# BMS_Carrier_-_Firmware_Contactor_Control.net
KiCad netlist of a schematic drawn in Altium Designer
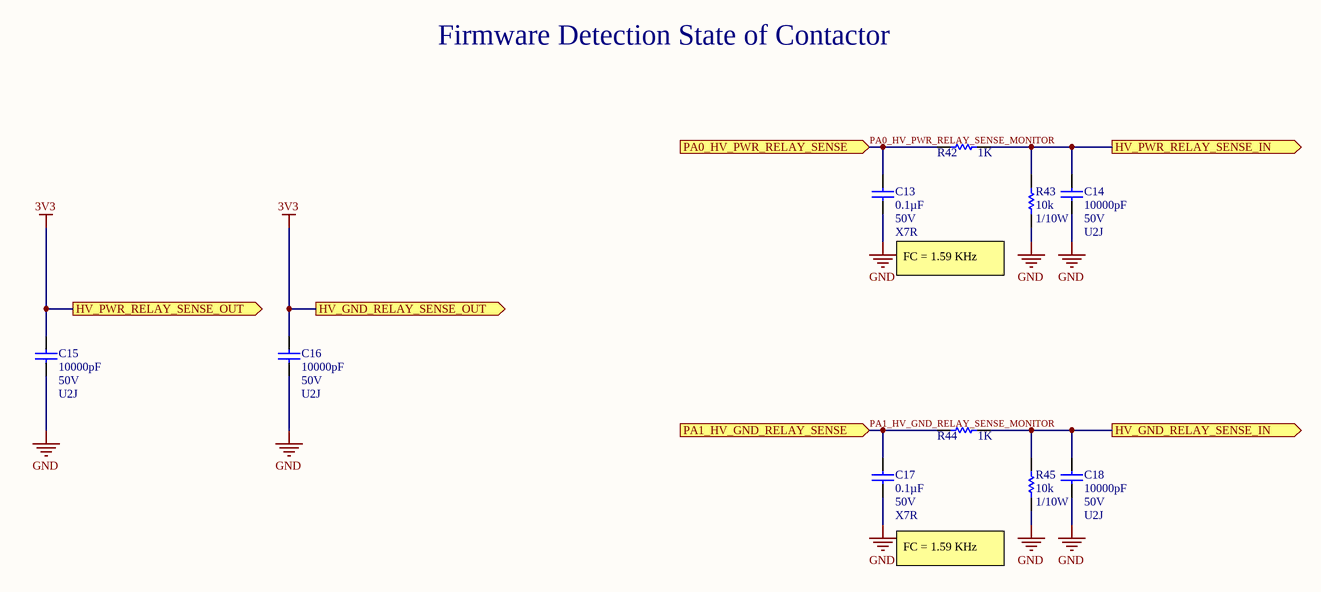
[diagram p0: BMS Carrier - Firmware Contactor Control.SchDoc]

(export (version "E")
  (design (tool "Eeschema 10.0.6"))
  (components
    (comp (ref "C13")
      (value "CAP CER 0.1UF 50V 10% X7R 0603")
      (footprint "CAP, 0603")
      (description "0.10µF ±10% 50V Ceramic Capacitor X7R 0603 (1608 Metric)")
      (fields
        (field (name "TOLERANCE") "±10%")
        (field (name "CAPACITANCE") "0.1µF")
        (field (name "VOLTAGE") "50V")
        (field (name "TEMPERATURE COEFFICIENT") "X7R")
      )
      (libsource (lib "Schematic Diagrams") (part "CAP CER 0.1UF 50V 10% X7R 0603"))
    )
    (comp (ref "C14")
      (value "CAP CER 10nF 50V 5% X7R 0603")
      (footprint "CAP, 0603")
      (description "10000pF ±5% 50V Ceramic Capacitor U2J 0603 (1608 Metric)")
      (fields
        (field (name "TOLERANCE") "±5%")
        (field (name "CAPACITANCE") "10000pF")
        (field (name "VOLTAGE") "50V")
        (field (name "TEMPERATURE COEFFICIENT") "U2J")
      )
      (libsource (lib "Schematic Diagrams") (part "CAP CER 10nF 50V 5% X7R 0603"))
    )
    (comp (ref "C15")
      (value "CAP CER 10nF 50V 5% X7R 0603")
      (footprint "CAP, 0603")
      (description "10000pF ±5% 50V Ceramic Capacitor U2J 0603 (1608 Metric)")
      (fields
        (field (name "TOLERANCE") "±5%")
        (field (name "CAPACITANCE") "10000pF")
        (field (name "VOLTAGE") "50V")
        (field (name "TEMPERATURE COEFFICIENT") "U2J")
      )
      (libsource (lib "Schematic Diagrams") (part "CAP CER 10nF 50V 5% X7R 0603"))
    )
    (comp (ref "C16")
      (value "CAP CER 10nF 50V 5% X7R 0603")
      (footprint "CAP, 0603")
      (description "10000pF ±5% 50V Ceramic Capacitor U2J 0603 (1608 Metric)")
      (fields
        (field (name "TOLERANCE") "±5%")
        (field (name "CAPACITANCE") "10000pF")
        (field (name "VOLTAGE") "50V")
        (field (name "TEMPERATURE COEFFICIENT") "U2J")
      )
      (libsource (lib "Schematic Diagrams") (part "CAP CER 10nF 50V 5% X7R 0603"))
    )
    (comp (ref "C17")
      (value "CAP CER 0.1UF 50V 10% X7R 0603")
      (footprint "CAP, 0603")
      (description "0.10µF ±10% 50V Ceramic Capacitor X7R 0603 (1608 Metric)")
      (fields
        (field (name "TOLERANCE") "±10%")
        (field (name "CAPACITANCE") "0.1µF")
        (field (name "VOLTAGE") "50V")
        (field (name "TEMPERATURE COEFFICIENT") "X7R")
      )
      (libsource (lib "Schematic Diagrams") (part "CAP CER 0.1UF 50V 10% X7R 0603"))
    )
    (comp (ref "C18")
      (value "CAP CER 10nF 50V 5% X7R 0603")
      (footprint "CAP, 0603")
      (description "10000pF ±5% 50V Ceramic Capacitor U2J 0603 (1608 Metric)")
      (fields
        (field (name "TOLERANCE") "±5%")
        (field (name "CAPACITANCE") "10000pF")
        (field (name "VOLTAGE") "50V")
        (field (name "TEMPERATURE COEFFICIENT") "U2J")
      )
      (libsource (lib "Schematic Diagrams") (part "CAP CER 10nF 50V 5% X7R 0603"))
    )
    (comp (ref "R42")
      (value "1K")
      (footprint "RES, 0603")
      (description "1k Ohm ±5% 0.1W, 1/10W Chip Resistor 0603 (1608 Metric)")
      (fields
        (field (name "MANUFACTURER") "Yageo")
        (field (name "MANUFACTURER PART NUMBER") "RC0603JR-071KL")
      )
      (libsource (lib "Schematic Diagrams") (part "RES 1K OHM 5% 1/10W 0603"))
    )
    (comp (ref "R43")
      (value "RES 10K OHM 1% 1/10W 0603")
      (footprint "RES, 0603")
      (description "RES SMD 10K OHM 1% 1/10W 0603")
      (fields
        (field (name "TOLERANCE") "±1%")
        (field (name "RESISTANCE") "10k")
        (field (name "POWER") "1/10W")
      )
      (libsource (lib "Schematic Diagrams") (part "RES 10K OHM 1% 1/10W 0603"))
    )
    (comp (ref "R44")
      (value "1K")
      (footprint "RES, 0603")
      (description "1k Ohm ±5% 0.1W, 1/10W Chip Resistor 0603 (1608 Metric)")
      (fields
        (field (name "MANUFACTURER") "Yageo")
        (field (name "MANUFACTURER PART NUMBER") "RC0603JR-071KL")
      )
      (libsource (lib "Schematic Diagrams") (part "RES 1K OHM 5% 1/10W 0603"))
    )
    (comp (ref "R45")
      (value "RES 10K OHM 1% 1/10W 0603")
      (footprint "RES, 0603")
      (description "RES SMD 10K OHM 1% 1/10W 0603")
      (fields
        (field (name "TOLERANCE") "±1%")
        (field (name "RESISTANCE") "10k")
        (field (name "POWER") "1/10W")
      )
      (libsource (lib "Schematic Diagrams") (part "RES 10K OHM 1% 1/10W 0603"))
    )
  )
  (nets
    (net (code "1") (name "/HV_GND_RELAY_SENSE_IN") (class "Default")
      (node (ref "C18") (pin "1") (pinfunction "1_1") (pintype "passive"))
      (node (ref "R44") (pin "2") (pinfunction "2_2") (pintype "passive"))
      (node (ref "R45") (pin "1") (pinfunction "1_1") (pintype "passive"))
    )
    (net (code "2") (name "/HV_PWR_RELAY_SENSE_IN") (class "Default")
      (node (ref "C14") (pin "1") (pinfunction "1_1") (pintype "passive"))
      (node (ref "R42") (pin "2") (pinfunction "2_2") (pintype "passive"))
      (node (ref "R43") (pin "1") (pinfunction "1_1") (pintype "passive"))
    )
    (net (code "3") (name "/PA0_HV_PWR_RELAY_SENSE_MONITOR") (class "Default")
      (node (ref "C13") (pin "1") (pinfunction "1_1") (pintype "passive"))
      (node (ref "R42") (pin "1") (pinfunction "1_1") (pintype "passive"))
    )
    (net (code "4") (name "/PA1_HV_GND_RELAY_SENSE_MONITOR") (class "Default")
      (node (ref "C17") (pin "1") (pinfunction "1_1") (pintype "passive"))
      (node (ref "R44") (pin "1") (pinfunction "1_1") (pintype "passive"))
    )
    (net (code "5") (name "3V3") (class "Default")
      (node (ref "C15") (pin "1") (pinfunction "1_1") (pintype "passive"))
      (node (ref "C16") (pin "1") (pinfunction "1_1") (pintype "passive"))
    )
    (net (code "6") (name "GND") (class "Default")
      (node (ref "C13") (pin "2") (pinfunction "2_2") (pintype "passive"))
      (node (ref "C14") (pin "2") (pinfunction "2_2") (pintype "passive"))
      (node (ref "C15") (pin "2") (pinfunction "2_2") (pintype "passive"))
      (node (ref "C16") (pin "2") (pinfunction "2_2") (pintype "passive"))
      (node (ref "C17") (pin "2") (pinfunction "2_2") (pintype "passive"))
      (node (ref "C18") (pin "2") (pinfunction "2_2") (pintype "passive"))
      (node (ref "R43") (pin "2") (pinfunction "2_2") (pintype "passive"))
      (node (ref "R45") (pin "2") (pinfunction "2_2") (pintype "passive"))
    )
  )
)
